# DC-DC-Brick.net
KiCad netlist of a schematic drawn in EAGLE
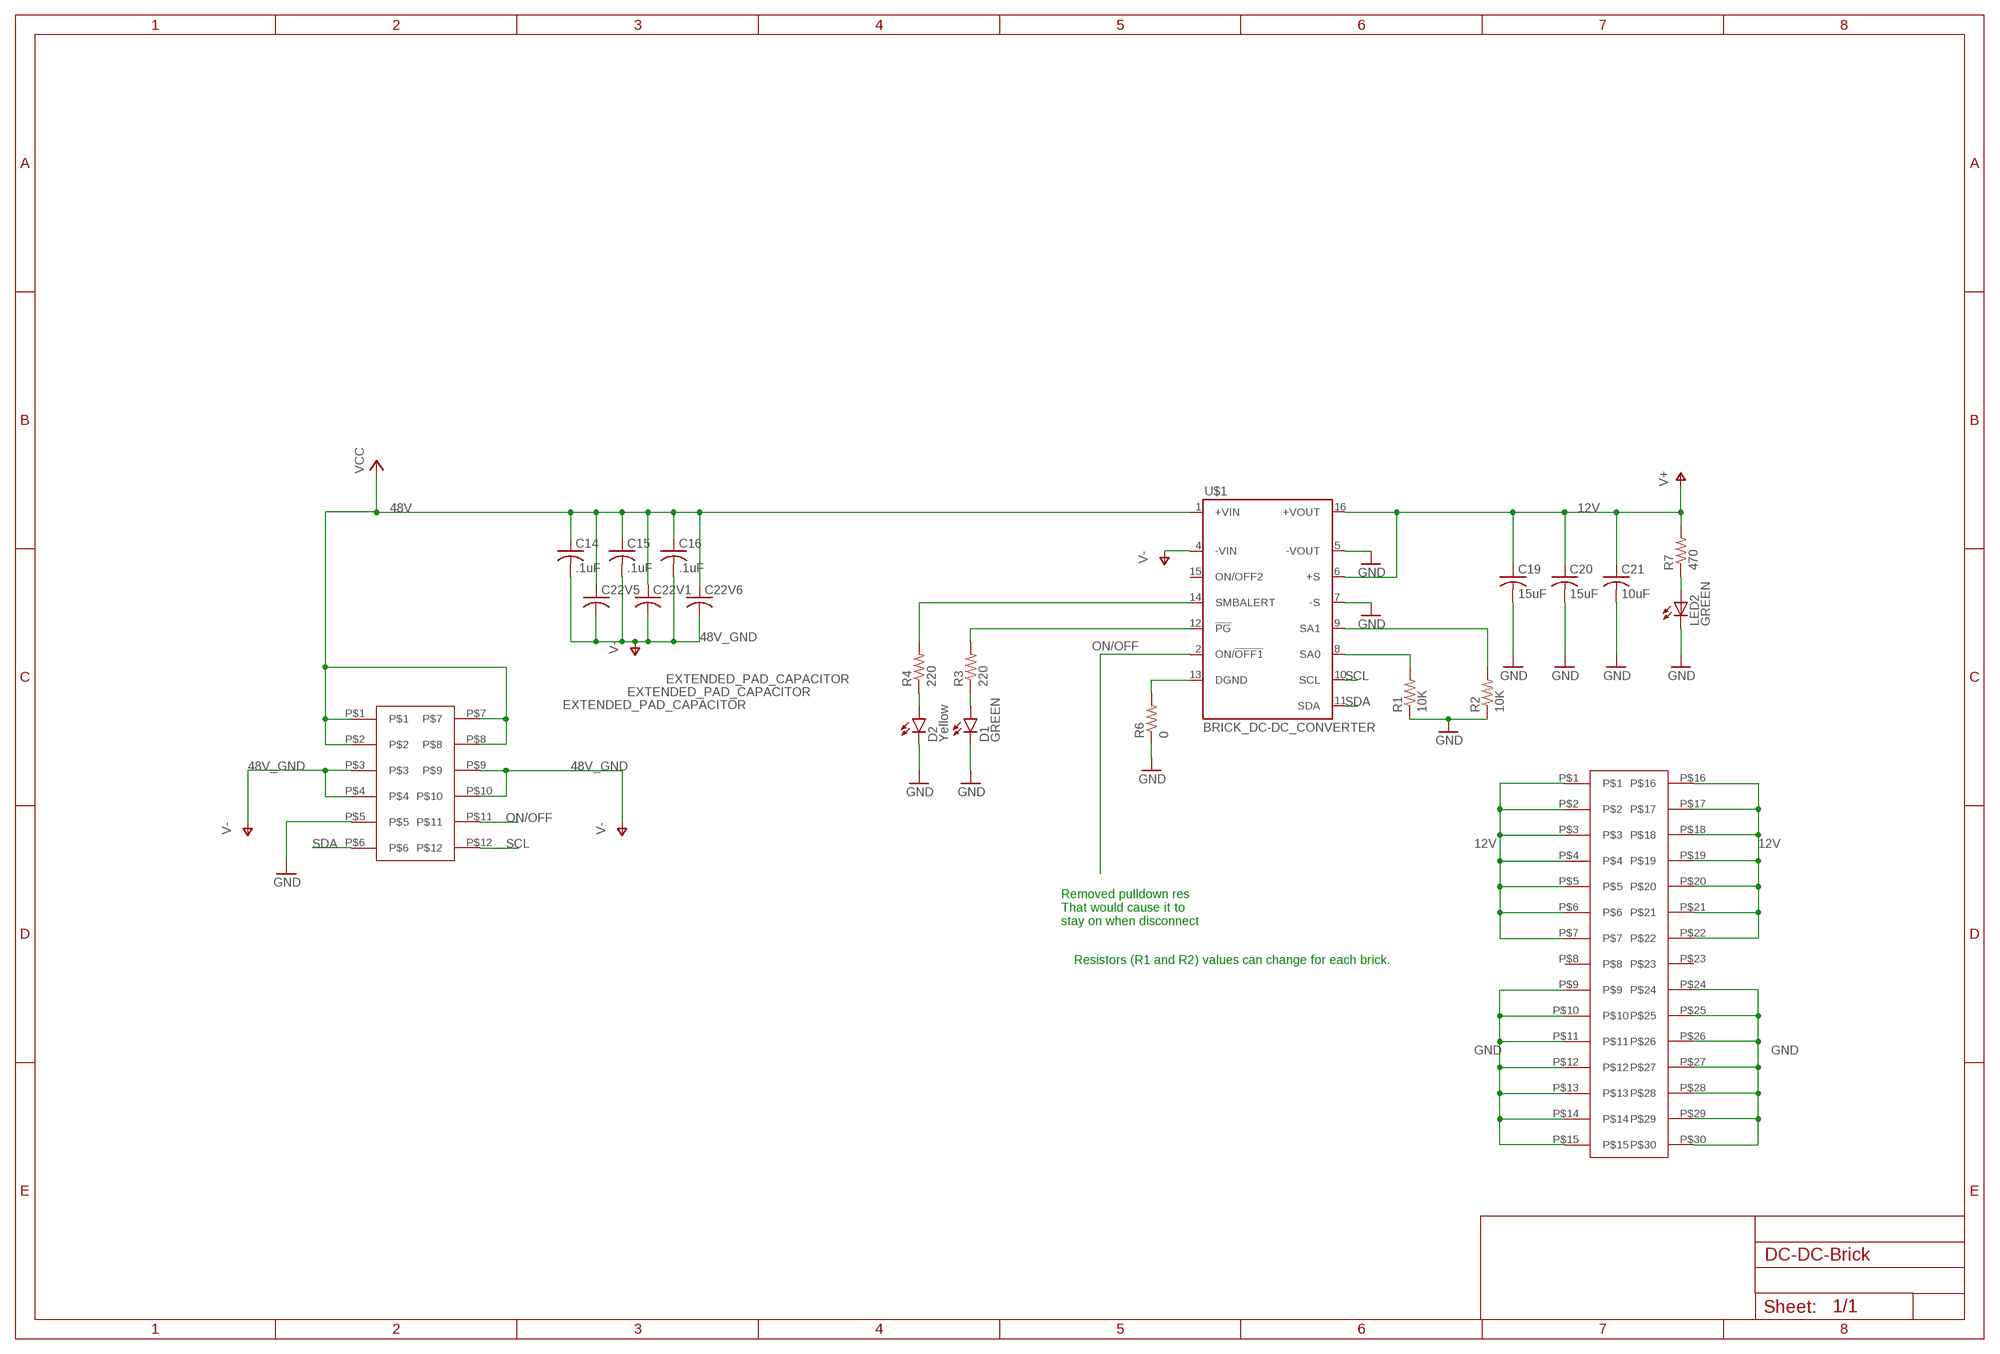
[diagram p0: schematic, sheet 1]

(export (version "E")
  (design (tool "Eeschema 10.0.6"))
  (components
    (comp (ref "C14")
      (value ".1uF")
      (footprint "eagle-import:C0603")
      (libsource (lib "eagle-import") (part "C-USC0603"))
    )
    (comp (ref "C15")
      (value ".1uF")
      (footprint "eagle-import:C0603")
      (libsource (lib "eagle-import") (part "C-USC0603"))
    )
    (comp (ref "C16")
      (value ".1uF")
      (footprint "eagle-import:C0603")
      (libsource (lib "eagle-import") (part "C-USC0603"))
    )
    (comp (ref "C19")
      (value "15uF")
      (footprint "eagle-import:C3216")
      (libsource (lib "eagle-import") (part "C-USC3216"))
    )
    (comp (ref "C20")
      (value "15uF")
      (footprint "eagle-import:C3216")
      (libsource (lib "eagle-import") (part "C-USC3216"))
    )
    (comp (ref "C21")
      (value "10uF")
      (footprint "eagle-import:C0603")
      (libsource (lib "eagle-import") (part "C-USC0603"))
    )
    (comp (ref "C22V1")
      (value "EXTENDED_PAD_CAPACITOR")
      (footprint "eagle-import:MODIFIED-NICHICON-UX-8X10")
      (libsource (lib "eagle-import") (part "EXTENDED_PAD_CAPACITOR"))
    )
    (comp (ref "C22V5")
      (value "EXTENDED_PAD_CAPACITOR")
      (footprint "eagle-import:MODIFIED-NICHICON-UX-8X10")
      (libsource (lib "eagle-import") (part "EXTENDED_PAD_CAPACITOR"))
    )
    (comp (ref "C22V6")
      (value "EXTENDED_PAD_CAPACITOR")
      (footprint "eagle-import:MODIFIED-NICHICON-UX-8X10")
      (libsource (lib "eagle-import") (part "EXTENDED_PAD_CAPACITOR"))
    )
    (comp (ref "D1")
      (value "GREEN")
      (footprint "eagle-import:LED-0603")
      (libsource (lib "eagle-import") (part "LED-GREEN0603"))
    )
    (comp (ref "D2")
      (value "Yellow")
      (footprint "eagle-import:LED-0603")
      (libsource (lib "eagle-import") (part "LED-YELLOW0603"))
    )
    (comp (ref "LED2")
      (value "GREEN")
      (footprint "eagle-import:LED-0603")
      (fields (field (name "PARTNO") "160-1446-1-ND"))
      (libsource (lib "eagle-import") (part "LED0603"))
    )
    (comp (ref "R1")
      (value "10K")
      (footprint "eagle-import:0603-RES")
      (libsource (lib "eagle-import") (part "10KOHM-1/10W-1%(0603)0603"))
    )
    (comp (ref "R2")
      (value "10K")
      (footprint "eagle-import:0603-RES")
      (libsource (lib "eagle-import") (part "10KOHM-1/10W-1%(0603)0603"))
    )
    (comp (ref "R3")
      (value "220")
      (footprint "eagle-import:0603-RES")
      (libsource (lib "eagle-import") (part "1KOHM-1/10W-1%(0603)"))
    )
    (comp (ref "R4")
      (value "220")
      (footprint "eagle-import:0603-RES")
      (libsource (lib "eagle-import") (part "1KOHM-1/10W-1%(0603)"))
    )
    (comp (ref "R6")
      (value "0")
      (footprint "eagle-import:0603-RES")
      (libsource (lib "eagle-import") (part "1KOHM-1/10W-1%(0603)"))
    )
    (comp (ref "R7")
      (value "470")
      (footprint "eagle-import:0603-RES")
      (libsource (lib "eagle-import") (part "470OHM1/10W1%(0603)"))
    )
    (comp (ref "U$1")
      (value "BRICK_DC-DC_CONVERTER")
      (footprint "eagle-import:BRICK_DC-DC_CONVERTER")
      (libsource (lib "eagle-import") (part "BRICK_DC-DC_CONVERTER"))
    )
    (comp (ref "U$2")
      (value "POWER_BRICK_CONNECTORS(2X6)")
      (footprint "eagle-import:POWER_BRICK_CONNECTORS(2X6)")
      (libsource (lib "eagle-import") (part "POWER_BRICK_CONNECTORS(2X6)"))
    )
    (comp (ref "U$3")
      (value "POWER_BRICK_CONNECTORS(2X15)")
      (footprint "eagle-import:POWER_BRICK_CONNECTORS(2X15)")
      (libsource (lib "eagle-import") (part "POWER_BRICK_CONNECTORS(2X15)"))
    )
  )
  (nets
    (net (code "1") (name "/ON{slash}OFF") (class "Default")
      (node (ref "U$1") (pin "2") (pinfunction "ON/~{OFF1}_2") (pintype "bidirectional"))
      (node (ref "U$2") (pin "P$11") (pinfunction "P$11_P$11") (pintype "bidirectional"))
    )
    (net (code "2") (name "/SCL") (class "Default")
      (node (ref "U$1") (pin "10") (pinfunction "SCL_10") (pintype "bidirectional"))
      (node (ref "U$2") (pin "P$12") (pinfunction "P$12_P$12") (pintype "bidirectional"))
    )
    (net (code "3") (name "/SDA") (class "Default")
      (node (ref "U$1") (pin "11") (pinfunction "SDA_11") (pintype "bidirectional"))
      (node (ref "U$2") (pin "P$6") (pinfunction "P$6_P$6") (pintype "bidirectional"))
    )
    (net (code "4") (name "GND") (class "Default")
      (node (ref "C19") (pin "2") (pinfunction "2_2") (pintype "passive"))
      (node (ref "C20") (pin "2") (pinfunction "2_2") (pintype "passive"))
      (node (ref "C21") (pin "2") (pinfunction "2_2") (pintype "passive"))
      (node (ref "D1") (pin "C") (pinfunction "C_C") (pintype "passive"))
      (node (ref "D2") (pin "C") (pinfunction "C_C") (pintype "passive"))
      (node (ref "LED2") (pin "C") (pinfunction "C_C") (pintype "passive"))
      (node (ref "R1") (pin "1") (pinfunction "1_1") (pintype "passive"))
      (node (ref "R2") (pin "1") (pinfunction "1_1") (pintype "passive"))
      (node (ref "R6") (pin "1") (pinfunction "1_1") (pintype "passive"))
      (node (ref "U$1") (pin "5") (pinfunction "-VOUT_5") (pintype "power_in"))
      (node (ref "U$1") (pin "7") (pinfunction "-S_7") (pintype "bidirectional"))
      (node (ref "U$2") (pin "P$5") (pinfunction "P$5_P$5") (pintype "bidirectional"))
      (node (ref "U$3") (pin "P$10") (pinfunction "P$10_P$10") (pintype "bidirectional"))
      (node (ref "U$3") (pin "P$11") (pinfunction "P$11_P$11") (pintype "bidirectional"))
      (node (ref "U$3") (pin "P$12") (pinfunction "P$12_P$12") (pintype "bidirectional"))
      (node (ref "U$3") (pin "P$13") (pinfunction "P$13_P$13") (pintype "bidirectional"))
      (node (ref "U$3") (pin "P$14") (pinfunction "P$14_P$14") (pintype "bidirectional"))
      (node (ref "U$3") (pin "P$15") (pinfunction "P$15_P$15") (pintype "bidirectional"))
      (node (ref "U$3") (pin "P$24") (pinfunction "P$24_P$24") (pintype "bidirectional"))
      (node (ref "U$3") (pin "P$25") (pinfunction "P$25_P$25") (pintype "bidirectional"))
      (node (ref "U$3") (pin "P$26") (pinfunction "P$26_P$26") (pintype "bidirectional"))
      (node (ref "U$3") (pin "P$27") (pinfunction "P$27_P$27") (pintype "bidirectional"))
      (node (ref "U$3") (pin "P$28") (pinfunction "P$28_P$28") (pintype "bidirectional"))
      (node (ref "U$3") (pin "P$29") (pinfunction "P$29_P$29") (pintype "bidirectional"))
      (node (ref "U$3") (pin "P$30") (pinfunction "P$30_P$30") (pintype "bidirectional"))
      (node (ref "U$3") (pin "P$9") (pinfunction "P$9_P$9") (pintype "bidirectional"))
    )
    (net (code "5") (name "Net-(D1-PadA)") (class "Default")
      (node (ref "D1") (pin "A") (pinfunction "A_A") (pintype "passive"))
      (node (ref "R3") (pin "1") (pinfunction "1_1") (pintype "passive"))
    )
    (net (code "6") (name "Net-(D2-PadA)") (class "Default")
      (node (ref "D2") (pin "A") (pinfunction "A_A") (pintype "passive"))
      (node (ref "R4") (pin "1") (pinfunction "1_1") (pintype "passive"))
    )
    (net (code "7") (name "Net-(LED2-PadA)") (class "Default")
      (node (ref "LED2") (pin "A") (pinfunction "A_A") (pintype "passive"))
      (node (ref "R7") (pin "1") (pinfunction "1_1") (pintype "passive"))
    )
    (net (code "8") (name "Net-(U$1-DGND)") (class "Default")
      (node (ref "R6") (pin "2") (pinfunction "2_2") (pintype "passive"))
      (node (ref "U$1") (pin "13") (pinfunction "DGND_13") (pintype "power_in"))
    )
    (net (code "9") (name "Net-(U$1-SA0)") (class "Default")
      (node (ref "R1") (pin "2") (pinfunction "2_2") (pintype "passive"))
      (node (ref "U$1") (pin "8") (pinfunction "SA0_8") (pintype "bidirectional"))
    )
    (net (code "10") (name "Net-(U$1-SA1)") (class "Default")
      (node (ref "R2") (pin "2") (pinfunction "2_2") (pintype "passive"))
      (node (ref "U$1") (pin "9") (pinfunction "SA1_9") (pintype "bidirectional"))
    )
    (net (code "11") (name "Net-(U$1-SMBALERT)") (class "Default")
      (node (ref "R4") (pin "2") (pinfunction "2_2") (pintype "passive"))
      (node (ref "U$1") (pin "14") (pinfunction "SMBALERT_14") (pintype "bidirectional"))
    )
    (net (code "12") (name "Net-(U$1-~{PG})") (class "Default")
      (node (ref "R3") (pin "2") (pinfunction "2_2") (pintype "passive"))
      (node (ref "U$1") (pin "12") (pinfunction "~{PG}_12") (pintype "bidirectional"))
    )
    (net (code "13") (name "V+") (class "Default")
      (node (ref "C19") (pin "1") (pinfunction "1_1") (pintype "passive"))
      (node (ref "C20") (pin "1") (pinfunction "1_1") (pintype "passive"))
      (node (ref "C21") (pin "1") (pinfunction "1_1") (pintype "passive"))
      (node (ref "R7") (pin "2") (pinfunction "2_2") (pintype "passive"))
      (node (ref "U$1") (pin "16") (pinfunction "+VOUT_16") (pintype "power_in"))
      (node (ref "U$1") (pin "6") (pinfunction "+S_6") (pintype "bidirectional"))
      (node (ref "U$3") (pin "P$1") (pinfunction "P$1_P$1") (pintype "bidirectional"))
      (node (ref "U$3") (pin "P$16") (pinfunction "P$16_P$16") (pintype "bidirectional"))
      (node (ref "U$3") (pin "P$17") (pinfunction "P$17_P$17") (pintype "bidirectional"))
      (node (ref "U$3") (pin "P$18") (pinfunction "P$18_P$18") (pintype "bidirectional"))
      (node (ref "U$3") (pin "P$19") (pinfunction "P$19_P$19") (pintype "bidirectional"))
      (node (ref "U$3") (pin "P$2") (pinfunction "P$2_P$2") (pintype "bidirectional"))
      (node (ref "U$3") (pin "P$20") (pinfunction "P$20_P$20") (pintype "bidirectional"))
      (node (ref "U$3") (pin "P$21") (pinfunction "P$21_P$21") (pintype "bidirectional"))
      (node (ref "U$3") (pin "P$22") (pinfunction "P$22_P$22") (pintype "bidirectional"))
      (node (ref "U$3") (pin "P$3") (pinfunction "P$3_P$3") (pintype "bidirectional"))
      (node (ref "U$3") (pin "P$4") (pinfunction "P$4_P$4") (pintype "bidirectional"))
      (node (ref "U$3") (pin "P$5") (pinfunction "P$5_P$5") (pintype "bidirectional"))
      (node (ref "U$3") (pin "P$6") (pinfunction "P$6_P$6") (pintype "bidirectional"))
      (node (ref "U$3") (pin "P$7") (pinfunction "P$7_P$7") (pintype "bidirectional"))
    )
    (net (code "14") (name "V-") (class "Default")
      (node (ref "C14") (pin "2") (pinfunction "2_2") (pintype "passive"))
      (node (ref "C15") (pin "2") (pinfunction "2_2") (pintype "passive"))
      (node (ref "C16") (pin "2") (pinfunction "2_2") (pintype "passive"))
      (node (ref "C22V1") (pin "P$1") (pinfunction "4_P$1") (pintype "passive"))
      (node (ref "C22V5") (pin "P$1") (pinfunction "4_P$1") (pintype "passive"))
      (node (ref "C22V6") (pin "P$1") (pinfunction "4_P$1") (pintype "passive"))
      (node (ref "U$1") (pin "4") (pinfunction "-VIN_4") (pintype "power_in"))
      (node (ref "U$2") (pin "P$10") (pinfunction "P$10_P$10") (pintype "bidirectional"))
      (node (ref "U$2") (pin "P$3") (pinfunction "P$3_P$3") (pintype "bidirectional"))
      (node (ref "U$2") (pin "P$4") (pinfunction "P$4_P$4") (pintype "bidirectional"))
      (node (ref "U$2") (pin "P$9") (pinfunction "P$9_P$9") (pintype "bidirectional"))
    )
    (net (code "15") (name "VCC") (class "Default")
      (node (ref "C14") (pin "1") (pinfunction "1_1") (pintype "passive"))
      (node (ref "C15") (pin "1") (pinfunction "1_1") (pintype "passive"))
      (node (ref "C16") (pin "1") (pinfunction "1_1") (pintype "passive"))
      (node (ref "C22V1") (pin "P$3") (pinfunction "3_P$3") (pintype "passive"))
      (node (ref "C22V5") (pin "P$3") (pinfunction "3_P$3") (pintype "passive"))
      (node (ref "C22V6") (pin "P$3") (pinfunction "3_P$3") (pintype "passive"))
      (node (ref "U$1") (pin "1") (pinfunction "+VIN_1") (pintype "power_in"))
      (node (ref "U$2") (pin "P$1") (pinfunction "P$1_P$1") (pintype "bidirectional"))
      (node (ref "U$2") (pin "P$2") (pinfunction "P$2_P$2") (pintype "bidirectional"))
      (node (ref "U$2") (pin "P$7") (pinfunction "P$7_P$7") (pintype "bidirectional"))
      (node (ref "U$2") (pin "P$8") (pinfunction "P$8_P$8") (pintype "bidirectional"))
    )
    (net (code "16") (name "unconnected-(U$1-ON{slash}OFF2-Pad15)") (class "Default")
      (node (ref "U$1") (pin "15") (pinfunction "ON/OFF2_15") (pintype "bidirectional"))
    )
    (net (code "17") (name "unconnected-(U$3-PadP$8)") (class "Default")
      (node (ref "U$3") (pin "P$8") (pinfunction "P$8_P$8") (pintype "bidirectional"))
    )
    (net (code "18") (name "unconnected-(U$3-PadP$23)") (class "Default")
      (node (ref "U$3") (pin "P$23") (pinfunction "P$23_P$23") (pintype "bidirectional"))
    )
  )
)
